# ice_drifter_6.net
KiCad netlist of a schematic drawn in EAGLE
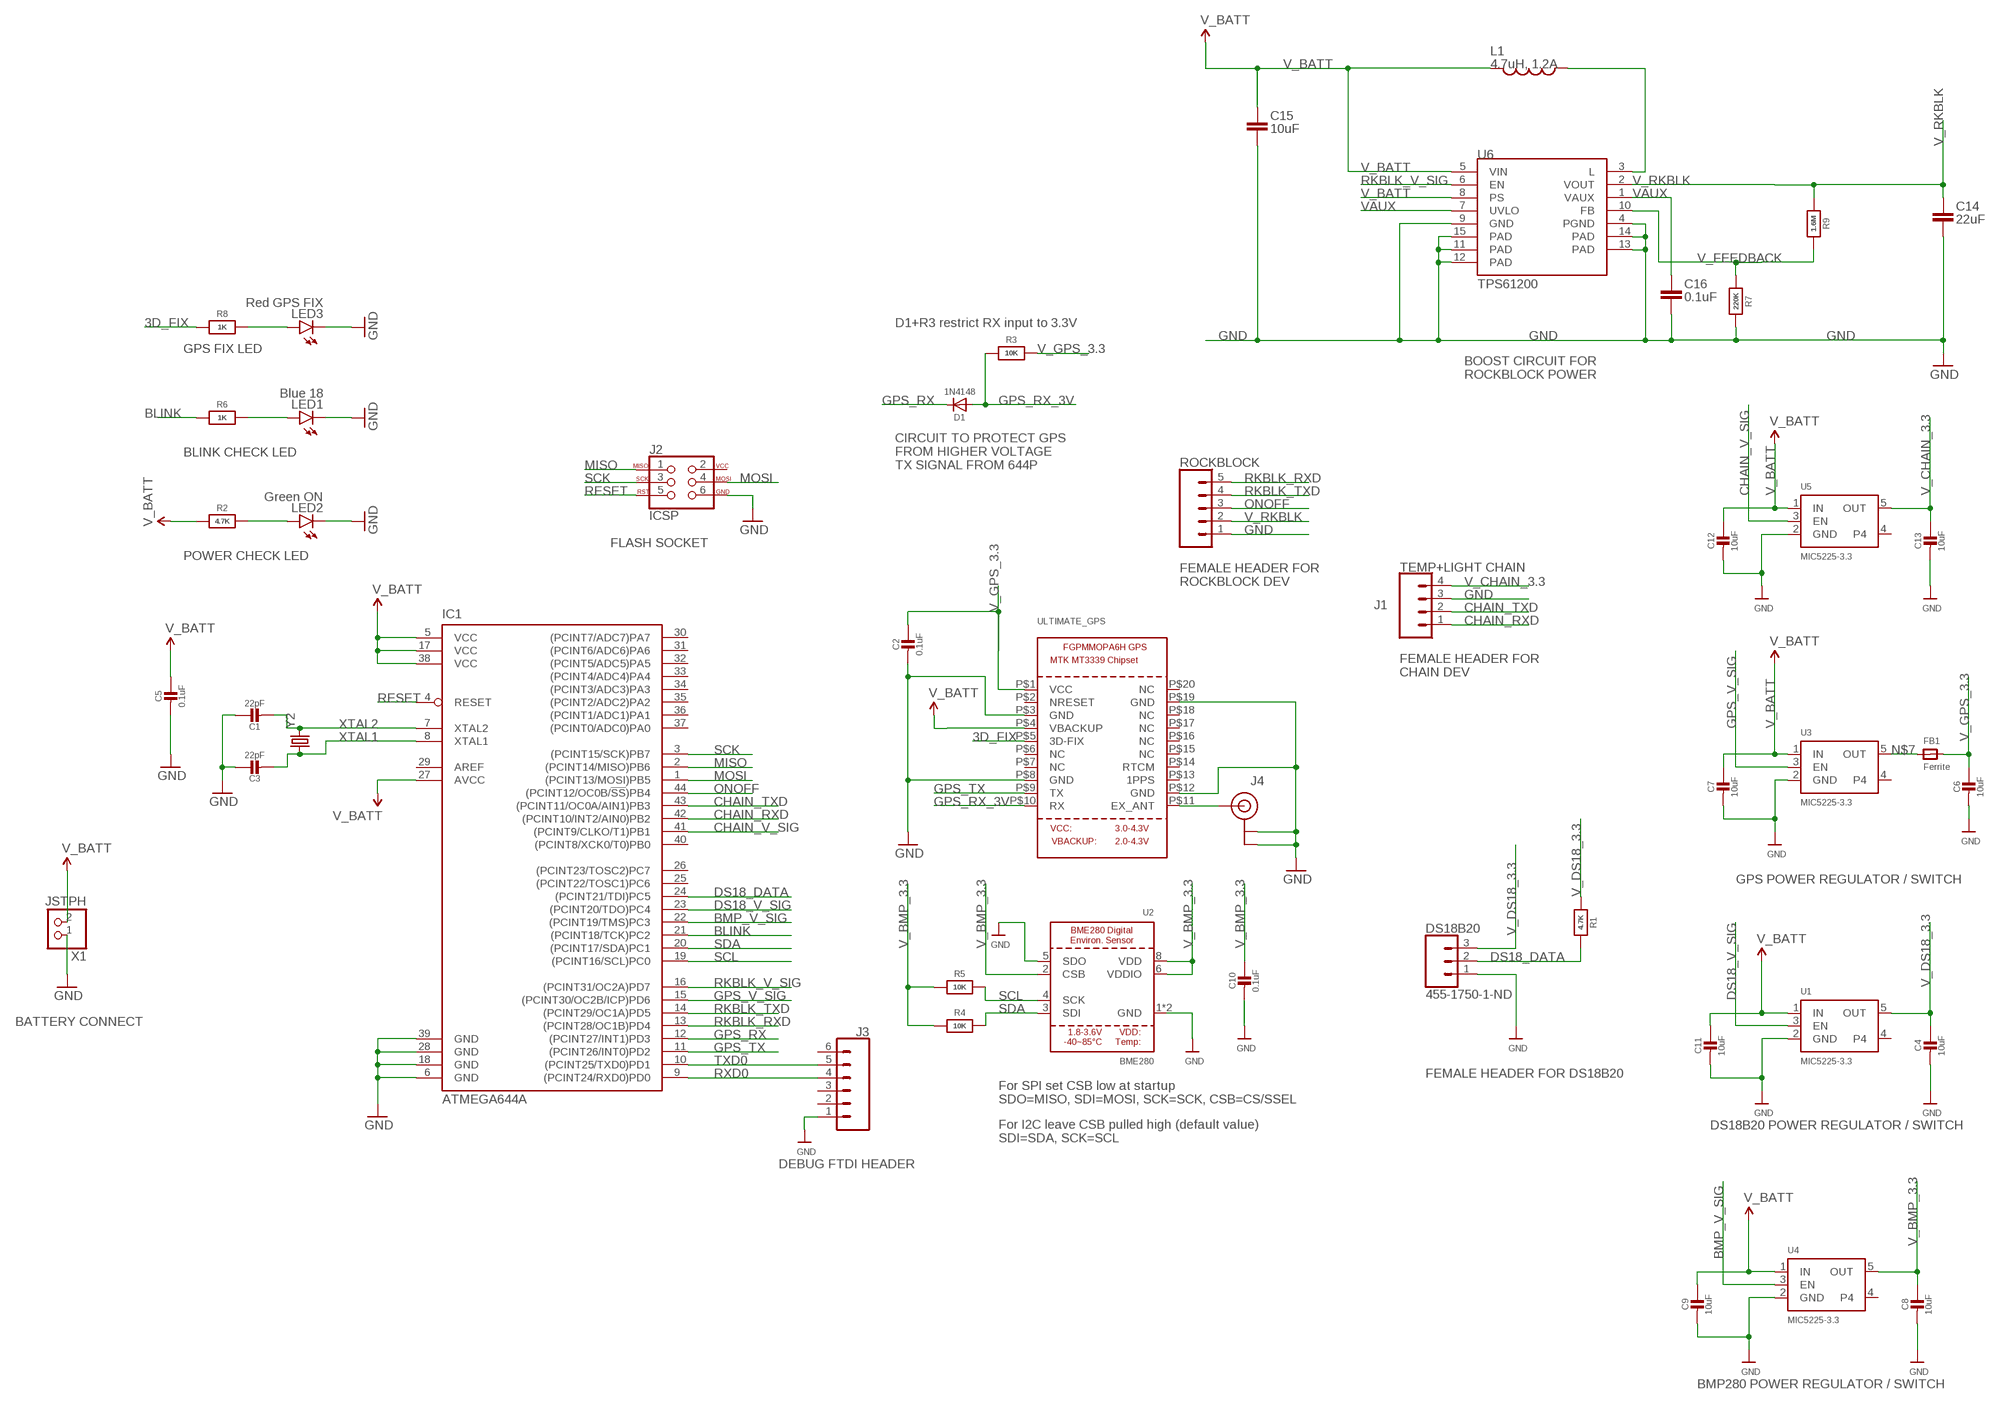
[diagram p0: schematic, sheet 1]

(export (version "E")
  (design (tool "Eeschema 10.0.6"))
  (components
    (comp (ref "C1")
      (value "22pF")
      (footprint "eagle-import:0805-NO@2")
      (libsource (lib "eagle-import") (part "CAP_CERAMIC0805-NOOUTLINE"))
    )
    (comp (ref "C2")
      (value "0.1uF")
      (footprint "eagle-import:0805-NO@2")
      (libsource (lib "eagle-import") (part "CAP_CERAMIC0805-NOOUTLINE"))
    )
    (comp (ref "C3")
      (value "22pF")
      (footprint "eagle-import:0805-NO@2")
      (libsource (lib "eagle-import") (part "CAP_CERAMIC0805-NOOUTLINE"))
    )
    (comp (ref "C4")
      (value "10uF")
      (footprint "eagle-import:0805-NO@2")
      (libsource (lib "eagle-import") (part "CAP_CERAMIC0805-NOOUTLINE"))
    )
    (comp (ref "C5")
      (value "0.1uF")
      (footprint "eagle-import:0805-NO@2")
      (libsource (lib "eagle-import") (part "CAP_CERAMIC0805-NOOUTLINE"))
    )
    (comp (ref "C6")
      (value "10uF")
      (footprint "eagle-import:0805-NO@2")
      (libsource (lib "eagle-import") (part "CAP_CERAMIC0805-NOOUTLINE"))
    )
    (comp (ref "C7")
      (value "10uF")
      (footprint "eagle-import:0805-NO@2")
      (libsource (lib "eagle-import") (part "CAP_CERAMIC0805-NOOUTLINE"))
    )
    (comp (ref "C8")
      (value "10uF")
      (footprint "eagle-import:0805-NO@2")
      (libsource (lib "eagle-import") (part "CAP_CERAMIC0805-NOOUTLINE"))
    )
    (comp (ref "C9")
      (value "10uF")
      (footprint "eagle-import:0805-NO@2")
      (libsource (lib "eagle-import") (part "CAP_CERAMIC0805-NOOUTLINE"))
    )
    (comp (ref "C10")
      (value "0.1uF")
      (footprint "eagle-import:0805-NO@2")
      (libsource (lib "eagle-import") (part "CAP_CERAMIC0805-NOOUTLINE"))
    )
    (comp (ref "C11")
      (value "10uF")
      (footprint "eagle-import:0805-NO@2")
      (libsource (lib "eagle-import") (part "CAP_CERAMIC0805-NOOUTLINE"))
    )
    (comp (ref "C12")
      (value "10uF")
      (footprint "eagle-import:0805-NO@2")
      (libsource (lib "eagle-import") (part "CAP_CERAMIC0805-NOOUTLINE"))
    )
    (comp (ref "C13")
      (value "10uF")
      (footprint "eagle-import:0805-NO@2")
      (libsource (lib "eagle-import") (part "CAP_CERAMIC0805-NOOUTLINE"))
    )
    (comp (ref "C14")
      (value "22uF")
      (footprint "eagle-import:0805")
      (libsource (lib "eagle-import") (part "CAP0805"))
    )
    (comp (ref "C15")
      (value "10uF")
      (footprint "eagle-import:1206")
      (libsource (lib "eagle-import") (part "CAP1206"))
    )
    (comp (ref "C16")
      (value "0.1uF")
      (footprint "eagle-import:0805")
      (libsource (lib "eagle-import") (part "CAP0805"))
    )
    (comp (ref "D1")
      (value "1N4148")
      (footprint "eagle-import:SOD-323")
      (libsource (lib "eagle-import") (part "DIODESOD-323"))
    )
    (comp (ref "DS18B20")
      (value "455-1750-1-ND")
      (footprint "eagle-import:1X03")
      (libsource (lib "eagle-import") (part "CONN_03"))
    )
    (comp (ref "FB1")
      (value "Ferrite")
      (footprint "eagle-import:0805-NO@1")
      (libsource (lib "eagle-import") (part "FERRITE-0805NO"))
    )
    (comp (ref "IC1")
      (value "ATMEGA644A")
      (footprint "eagle-import:TQFP44")
      (fields (field (name "MPN") "ATMEGA644PV-10AU"))
      (libsource (lib "eagle-import") (part "ATMEGA644A"))
    )
    (comp (ref "J1")
      (value "TEMP+LIGHT CHAIN")
      (footprint "eagle-import:1X04")
      (libsource (lib "eagle-import") (part "CONN_04"))
    )
    (comp (ref "J2")
      (value "ICSP")
      (footprint "eagle-import:2X3-NS")
      (libsource (lib "eagle-import") (part "AVR_SPI_PROG_3X2NS"))
    )
    (comp (ref "J3")
      (value "CONN_06SILK_FEMALE_PTH")
      (footprint "eagle-import:1X06")
      (libsource (lib "eagle-import") (part "CONN_06SILK_FEMALE_PTH"))
    )
    (comp (ref "J4")
      (value "U.FL")
      (footprint "eagle-import:U.FL")
      (libsource (lib "eagle-import") (part "U.FL"))
    )
    (comp (ref "L1")
      (value "4.7uH, 1.2A")
      (footprint "eagle-import:CDRH2D09")
      (libsource (lib "eagle-import") (part "INDUCTOR."))
    )
    (comp (ref "LED1")
      (value "Blue 18")
      (footprint "eagle-import:LED-1206")
      (libsource (lib "eagle-import") (part "LED1206"))
    )
    (comp (ref "LED2")
      (value "Green ON")
      (footprint "eagle-import:LED-1206")
      (libsource (lib "eagle-import") (part "LED1206"))
    )
    (comp (ref "LED3")
      (value "Red GPS FIX")
      (footprint "eagle-import:LED-1206")
      (libsource (lib "eagle-import") (part "LED1206"))
    )
    (comp (ref "R1")
      (value "4.7K")
      (footprint "eagle-import:0805-NO")
      (libsource (lib "eagle-import") (part "RESISTOR0805_NOOUTLINE"))
    )
    (comp (ref "R2")
      (value "4.7K")
      (footprint "eagle-import:0805-NO")
      (libsource (lib "eagle-import") (part "RESISTOR0805_NOOUTLINE"))
    )
    (comp (ref "R3")
      (value "10K")
      (footprint "eagle-import:0805-NO")
      (libsource (lib "eagle-import") (part "RESISTOR0805_NOOUTLINE"))
    )
    (comp (ref "R4")
      (value "10K")
      (footprint "eagle-import:0805-NO")
      (libsource (lib "eagle-import") (part "RESISTOR0805_NOOUTLINE"))
    )
    (comp (ref "R5")
      (value "10K")
      (footprint "eagle-import:0805-NO")
      (libsource (lib "eagle-import") (part "RESISTOR0805_NOOUTLINE"))
    )
    (comp (ref "R6")
      (value "1K")
      (footprint "eagle-import:0805-NO")
      (libsource (lib "eagle-import") (part "RESISTOR0805_NOOUTLINE"))
    )
    (comp (ref "R7")
      (value "220K")
      (footprint "eagle-import:0805-NO")
      (libsource (lib "eagle-import") (part "RESISTOR0805_NOOUTLINE"))
    )
    (comp (ref "R8")
      (value "1K")
      (footprint "eagle-import:0805-NO")
      (libsource (lib "eagle-import") (part "RESISTOR0805_NOOUTLINE"))
    )
    (comp (ref "R9")
      (value "1.6M")
      (footprint "eagle-import:0805-NO")
      (libsource (lib "eagle-import") (part "RESISTOR0805_NOOUTLINE"))
    )
    (comp (ref "ROCKBLOCK")
      (value "CONN_05")
      (footprint "eagle-import:1X05")
      (libsource (lib "eagle-import") (part "CONN_05"))
    )
    (comp (ref "U1")
      (value "MIC5225-3.3")
      (footprint "eagle-import:SOT23-5")
      (libsource (lib "eagle-import") (part "VREG_SOT23-5"))
    )
    (comp (ref "U2")
      (value "BME280")
      (footprint "eagle-import:BME280")
      (libsource (lib "eagle-import") (part "BME280"))
    )
    (comp (ref "U3")
      (value "MIC5225-3.3")
      (footprint "eagle-import:SOT23-5")
      (libsource (lib "eagle-import") (part "VREG_SOT23-5"))
    )
    (comp (ref "U4")
      (value "MIC5225-3.3")
      (footprint "eagle-import:SOT23-5")
      (libsource (lib "eagle-import") (part "VREG_SOT23-5"))
    )
    (comp (ref "U5")
      (value "MIC5225-3.3")
      (footprint "eagle-import:SOT23-5")
      (libsource (lib "eagle-import") (part "VREG_SOT23-5"))
    )
    (comp (ref "U6")
      (value "TPS61200")
      (footprint "eagle-import:QFN-10_PAD")
      (libsource (lib "eagle-import") (part "TPS61200"))
    )
    (comp (ref "ULTIMATE_GPS")
      (value "GPS_FGPMMOPA6H")
      (footprint "eagle-import:FGPMMOPA6H")
      (libsource (lib "eagle-import") (part "GPS_FGPMMOPA6H"))
    )
    (comp (ref "X1")
      (value "JSTPH")
      (footprint "eagle-import:JSTPH2")
      (libsource (lib "eagle-import") (part "CON_JST_PH_2PIN"))
    )
    (comp (ref "Y2")
      (value "CRYSTALTXC-7A")
      (footprint "eagle-import:CRYSTAL-TXC-7A")
      (libsource (lib "eagle-import") (part "CRYSTALTXC-7A"))
    )
  )
  (nets
    (net (code "1") (name "/3D_FIX") (class "Default")
      (node (ref "R8") (pin "1") (pinfunction "1_1") (pintype "passive"))
      (node (ref "ULTIMATE_GPS") (pin "P$5") (pinfunction "3D-FIX_P$5") (pintype "bidirectional"))
    )
    (net (code "2") (name "/BLINK") (class "Default")
      (node (ref "IC1") (pin "21") (pinfunction "(PCINT18/TCK)PC2_21") (pintype "output"))
      (node (ref "R6") (pin "1") (pinfunction "1_1") (pintype "passive"))
    )
    (net (code "3") (name "/BMP_V_SIG") (class "Default")
      (node (ref "IC1") (pin "22") (pinfunction "(PCINT19/TMS)PC3_22") (pintype "output"))
      (node (ref "U4") (pin "3") (pinfunction "EN_3") (pintype "input"))
    )
    (net (code "4") (name "/CHAIN_RXD") (class "Default")
      (node (ref "IC1") (pin "42") (pinfunction "(PCINT10/INT2/AIN0)PB2_42") (pintype "bidirectional"))
      (node (ref "J1") (pin "1") (pinfunction "1_1") (pintype "passive"))
    )
    (net (code "5") (name "/CHAIN_TXD") (class "Default")
      (node (ref "IC1") (pin "43") (pinfunction "(PCINT11/OC0A/AIN1)PB3_43") (pintype "bidirectional"))
      (node (ref "J1") (pin "2") (pinfunction "2_2") (pintype "passive"))
    )
    (net (code "6") (name "/CHAIN_V_SIG") (class "Default")
      (node (ref "IC1") (pin "41") (pinfunction "(PCINT9/CLKO/T1)PB1_41") (pintype "bidirectional"))
      (node (ref "U5") (pin "3") (pinfunction "EN_3") (pintype "input"))
    )
    (net (code "7") (name "/DS18_DATA") (class "Default")
      (node (ref "DS18B20") (pin "2") (pinfunction "2_2") (pintype "passive"))
      (node (ref "IC1") (pin "24") (pinfunction "(PCINT21/TDI)PC5_24") (pintype "output"))
      (node (ref "R1") (pin "2") (pinfunction "2_2") (pintype "passive"))
    )
    (net (code "8") (name "/DS18_V_SIG") (class "Default")
      (node (ref "IC1") (pin "23") (pinfunction "(PCINT20/TDO)PC4_23") (pintype "output"))
      (node (ref "U1") (pin "3") (pinfunction "EN_3") (pintype "input"))
    )
    (net (code "9") (name "/GPS_RX") (class "Default")
      (node (ref "D1") (pin "C") (pinfunction "C_C") (pintype "passive"))
      (node (ref "IC1") (pin "12") (pinfunction "(PCINT27/INT1)PD3_12") (pintype "bidirectional"))
    )
    (net (code "10") (name "/GPS_RX_3V") (class "Default")
      (node (ref "D1") (pin "A") (pinfunction "A_A") (pintype "passive"))
      (node (ref "R3") (pin "1") (pinfunction "1_1") (pintype "passive"))
      (node (ref "ULTIMATE_GPS") (pin "P$10") (pinfunction "RX_P$10") (pintype "bidirectional"))
    )
    (net (code "11") (name "/GPS_TX") (class "Default")
      (node (ref "IC1") (pin "11") (pinfunction "(PCINT26/INT0)PD2_11") (pintype "bidirectional"))
      (node (ref "ULTIMATE_GPS") (pin "P$9") (pinfunction "TX_P$9") (pintype "bidirectional"))
    )
    (net (code "12") (name "/GPS_V_SIG") (class "Default")
      (node (ref "IC1") (pin "15") (pinfunction "(PCINT30/OC2B/ICP)PD6_15") (pintype "bidirectional"))
      (node (ref "U3") (pin "3") (pinfunction "EN_3") (pintype "input"))
    )
    (net (code "13") (name "/MISO") (class "Default")
      (node (ref "IC1") (pin "2") (pinfunction "(PCINT14/MISO)PB6_2") (pintype "bidirectional"))
      (node (ref "J2") (pin "1") (pinfunction "1_1") (pintype "passive"))
    )
    (net (code "14") (name "/MOSI") (class "Default")
      (node (ref "IC1") (pin "1") (pinfunction "(PCINT13/MOSI)PB5_1") (pintype "bidirectional"))
      (node (ref "J2") (pin "4") (pinfunction "4_4") (pintype "passive"))
    )
    (net (code "15") (name "/N$7") (class "Default")
      (node (ref "FB1") (pin "1") (pinfunction "P$1_1") (pintype "passive"))
      (node (ref "U3") (pin "5") (pinfunction "OUT_5") (pintype "power_in"))
    )
    (net (code "16") (name "/ONOFF") (class "Default")
      (node (ref "IC1") (pin "44") (pinfunction "(PCINT12/OC0B/~{SS})PB4_44") (pintype "bidirectional"))
      (node (ref "ROCKBLOCK") (pin "3") (pinfunction "3_3") (pintype "passive"))
    )
    (net (code "17") (name "/RESET") (class "Default")
      (node (ref "IC1") (pin "4") (pinfunction "RESET_4") (pintype "input"))
      (node (ref "J2") (pin "5") (pinfunction "5_5") (pintype "passive"))
    )
    (net (code "18") (name "/RKBLK_RXD") (class "Default")
      (node (ref "IC1") (pin "13") (pinfunction "(PCINT28/OC1B)PD4_13") (pintype "bidirectional"))
      (node (ref "ROCKBLOCK") (pin "5") (pinfunction "5_5") (pintype "passive"))
    )
    (net (code "19") (name "/RKBLK_TXD") (class "Default")
      (node (ref "IC1") (pin "14") (pinfunction "(PCINT29/OC1A)PD5_14") (pintype "bidirectional"))
      (node (ref "ROCKBLOCK") (pin "4") (pinfunction "4_4") (pintype "passive"))
    )
    (net (code "20") (name "/RKBLK_V_SIG") (class "Default")
      (node (ref "IC1") (pin "16") (pinfunction "(PCINT31/OC2A)PD7_16") (pintype "bidirectional"))
      (node (ref "U6") (pin "6") (pinfunction "EN_6") (pintype "input"))
    )
    (net (code "21") (name "/RXD0") (class "Default")
      (node (ref "IC1") (pin "9") (pinfunction "(PCINT24/RXD0)PD0_9") (pintype "bidirectional"))
      (node (ref "J3") (pin "4") (pinfunction "4_4") (pintype "passive"))
    )
    (net (code "22") (name "/SCK") (class "Default")
      (node (ref "IC1") (pin "3") (pinfunction "(PCINT15/SCK)PB7_3") (pintype "bidirectional"))
      (node (ref "J2") (pin "3") (pinfunction "3_3") (pintype "passive"))
    )
    (net (code "23") (name "/SCL") (class "Default")
      (node (ref "IC1") (pin "19") (pinfunction "(PCINT16/SCL)PC0_19") (pintype "output"))
      (node (ref "R5") (pin "2") (pinfunction "2_2") (pintype "passive"))
      (node (ref "U2") (pin "4") (pinfunction "SCK_4") (pintype "input"))
    )
    (net (code "24") (name "/SDA") (class "Default")
      (node (ref "IC1") (pin "20") (pinfunction "(PCINT17/SDA)PC1_20") (pintype "output"))
      (node (ref "R4") (pin "2") (pinfunction "2_2") (pintype "passive"))
      (node (ref "U2") (pin "3") (pinfunction "SDI_3") (pintype "input"))
    )
    (net (code "25") (name "/TXD0") (class "Default")
      (node (ref "IC1") (pin "10") (pinfunction "(PCINT25/TXD0)PD1_10") (pintype "bidirectional"))
      (node (ref "J3") (pin "5") (pinfunction "5_5") (pintype "passive"))
    )
    (net (code "26") (name "/VAUX") (class "Default")
      (node (ref "C16") (pin "1") (pinfunction "1_1") (pintype "passive"))
      (node (ref "U6") (pin "1") (pinfunction "VAUX_1") (pintype "passive"))
      (node (ref "U6") (pin "7") (pinfunction "UVLO_7") (pintype "passive"))
    )
    (net (code "27") (name "/V_BMP_3.3") (class "Default")
      (node (ref "C10") (pin "1") (pinfunction "1_1") (pintype "passive"))
      (node (ref "C8") (pin "1") (pinfunction "1_1") (pintype "passive"))
      (node (ref "R4") (pin "1") (pinfunction "1_1") (pintype "passive"))
      (node (ref "R5") (pin "1") (pinfunction "1_1") (pintype "passive"))
      (node (ref "U2") (pin "2") (pinfunction "CSB_2") (pintype "input"))
      (node (ref "U2") (pin "6") (pinfunction "VDDIO_6") (pintype "power_in"))
      (node (ref "U2") (pin "8") (pinfunction "VDD_8") (pintype "power_in"))
      (node (ref "U4") (pin "5") (pinfunction "OUT_5") (pintype "power_in"))
    )
    (net (code "28") (name "/V_CHAIN_3.3") (class "Default")
      (node (ref "C13") (pin "1") (pinfunction "1_1") (pintype "passive"))
      (node (ref "J1") (pin "4") (pinfunction "4_4") (pintype "passive"))
      (node (ref "U5") (pin "5") (pinfunction "OUT_5") (pintype "power_in"))
    )
    (net (code "29") (name "/V_DS18_3.3") (class "Default")
      (node (ref "C4") (pin "1") (pinfunction "1_1") (pintype "passive"))
      (node (ref "DS18B20") (pin "3") (pinfunction "3_3") (pintype "passive"))
      (node (ref "R1") (pin "1") (pinfunction "1_1") (pintype "passive"))
      (node (ref "U1") (pin "5") (pinfunction "OUT_5") (pintype "power_in"))
    )
    (net (code "30") (name "/V_FEEDBACK") (class "Default")
      (node (ref "R7") (pin "1") (pinfunction "1_1") (pintype "passive"))
      (node (ref "R9") (pin "2") (pinfunction "2_2") (pintype "passive"))
      (node (ref "U6") (pin "10") (pinfunction "FB_10") (pintype "passive"))
    )
    (net (code "31") (name "/V_GPS_3.3") (class "Default")
      (node (ref "C2") (pin "1") (pinfunction "1_1") (pintype "passive"))
      (node (ref "C6") (pin "1") (pinfunction "1_1") (pintype "passive"))
      (node (ref "FB1") (pin "2") (pinfunction "P$2_2") (pintype "passive"))
      (node (ref "R3") (pin "2") (pinfunction "2_2") (pintype "passive"))
      (node (ref "ULTIMATE_GPS") (pin "P$1") (pinfunction "VCC_P$1") (pintype "bidirectional"))
    )
    (net (code "32") (name "/V_RKBLK") (class "Default")
      (node (ref "C14") (pin "1") (pinfunction "1_1") (pintype "passive"))
      (node (ref "R9") (pin "1") (pinfunction "1_1") (pintype "passive"))
      (node (ref "ROCKBLOCK") (pin "2") (pinfunction "2_2") (pintype "passive"))
      (node (ref "U6") (pin "2") (pinfunction "VOUT_2") (pintype "passive"))
    )
    (net (code "33") (name "/XTAL1") (class "Default")
      (node (ref "C3") (pin "2") (pinfunction "2_2") (pintype "passive"))
      (node (ref "IC1") (pin "8") (pinfunction "XTAL1_8") (pintype "bidirectional"))
      (node (ref "Y2") (pin "P$1") (pinfunction "1_P$1") (pintype "passive"))
    )
    (net (code "34") (name "/XTAL2") (class "Default")
      (node (ref "C1") (pin "2") (pinfunction "2_2") (pintype "passive"))
      (node (ref "IC1") (pin "7") (pinfunction "XTAL2_7") (pintype "bidirectional"))
      (node (ref "Y2") (pin "P$2") (pinfunction "2_P$2") (pintype "passive"))
    )
    (net (code "35") (name "GND") (class "Default")
      (node (ref "C1") (pin "1") (pinfunction "1_1") (pintype "passive"))
      (node (ref "C10") (pin "2") (pinfunction "2_2") (pintype "passive"))
      (node (ref "C11") (pin "2") (pinfunction "2_2") (pintype "passive"))
      (node (ref "C12") (pin "2") (pinfunction "2_2") (pintype "passive"))
      (node (ref "C13") (pin "2") (pinfunction "2_2") (pintype "passive"))
      (node (ref "C14") (pin "2") (pinfunction "2_2") (pintype "passive"))
      (node (ref "C15") (pin "2") (pinfunction "2_2") (pintype "passive"))
      (node (ref "C16") (pin "2") (pinfunction "2_2") (pintype "passive"))
      (node (ref "C2") (pin "2") (pinfunction "2_2") (pintype "passive"))
      (node (ref "C3") (pin "1") (pinfunction "1_1") (pintype "passive"))
      (node (ref "C4") (pin "2") (pinfunction "2_2") (pintype "passive"))
      (node (ref "C5") (pin "2") (pinfunction "2_2") (pintype "passive"))
      (node (ref "C6") (pin "2") (pinfunction "2_2") (pintype "passive"))
      (node (ref "C7") (pin "2") (pinfunction "2_2") (pintype "passive"))
      (node (ref "C8") (pin "2") (pinfunction "2_2") (pintype "passive"))
      (node (ref "C9") (pin "2") (pinfunction "2_2") (pintype "passive"))
      (node (ref "DS18B20") (pin "1") (pinfunction "1_1") (pintype "passive"))
      (node (ref "IC1") (pin "18") (pinfunction "GND_18") (pintype "power_in"))
      (node (ref "IC1") (pin "28") (pinfunction "GND_28") (pintype "power_in"))
      (node (ref "IC1") (pin "39") (pinfunction "GND_39") (pintype "power_in"))
      (node (ref "IC1") (pin "6") (pinfunction "GND_6") (pintype "power_in"))
      (node (ref "J1") (pin "3") (pinfunction "3_3") (pintype "passive"))
      (node (ref "J2") (pin "6") (pinfunction "6_6") (pintype "passive"))
      (node (ref "J3") (pin "1") (pinfunction "1_1") (pintype "passive"))
      (node (ref "J4") (pin "1") (pinfunction "GND_1") (pintype "bidirectional"))
      (node (ref "J4") (pin "2") (pinfunction "GND_2") (pintype "bidirectional"))
      (node (ref "LED1") (pin "C") (pinfunction "C_C") (pintype "passive"))
      (node (ref "LED2") (pin "C") (pinfunction "C_C") (pintype "passive"))
      (node (ref "LED3") (pin "C") (pinfunction "C_C") (pintype "passive"))
      (node (ref "R7") (pin "2") (pinfunction "2_2") (pintype "passive"))
      (node (ref "ROCKBLOCK") (pin "1") (pinfunction "1_1") (pintype "passive"))
      (node (ref "U1") (pin "2") (pinfunction "GND_2") (pintype "power_in"))
      (node (ref "U2") (pin "1") (pinfunction "GND_1") (pintype "power_in"))
      (node (ref "U2") (pin "5") (pinfunction "SDO_5") (pintype "output"))
      (node (ref "U2") (pin "7") (pinfunction "GND_7") (pintype "power_in"))
      (node (ref "U3") (pin "2") (pinfunction "GND_2") (pintype "power_in"))
      (node (ref "U4") (pin "2") (pinfunction "GND_2") (pintype "power_in"))
      (node (ref "U5") (pin "2") (pinfunction "GND_2") (pintype "power_in"))
      (node (ref "U6") (pin "11") (pinfunction "PAD_11") (pintype "power_in"))
      (node (ref "U6") (pin "12") (pinfunction "PAD_12") (pintype "power_in"))
      (node (ref "U6") (pin "13") (pinfunction "PAD_13") (pintype "power_in"))
      (node (ref "U6") (pin "14") (pinfunction "PAD_14") (pintype "power_in"))
      (node (ref "U6") (pin "15") (pinfunction "PAD_15") (pintype "power_in"))
      (node (ref "U6") (pin "4") (pinfunction "PGND_4") (pintype "power_in"))
      (node (ref "U6") (pin "9") (pinfunction "GND_9") (pintype "power_in"))
      (node (ref "ULTIMATE_GPS") (pin "P$12") (pinfunction "GND_P$12") (pintype "bidirectional"))
      (node (ref "ULTIMATE_GPS") (pin "P$19") (pinfunction "GND_P$19") (pintype "bidirectional"))
      (node (ref "ULTIMATE_GPS") (pin "P$3") (pinfunction "GND_P$3") (pintype "bidirectional"))
      (node (ref "ULTIMATE_GPS") (pin "P$8") (pinfunction "GND_P$8") (pintype "bidirectional"))
      (node (ref "X1") (pin "1") (pinfunction "1_1") (pintype "passive"))
    )
    (net (code "36") (name "Net-(J4-SIGNAL)") (class "Default")
      (node (ref "J4") (pin "FEED") (pinfunction "SIGNAL_FEED") (pintype "bidirectional"))
      (node (ref "ULTIMATE_GPS") (pin "P$11") (pinfunction "EX_ANT_P$11") (pintype "bidirectional"))
    )
    (net (code "37") (name "Net-(L1-1)") (class "Default")
      (node (ref "L1") (pin "P$1") (pinfunction "1_P$1") (pintype "passive"))
      (node (ref "U6") (pin "3") (pinfunction "L_3") (pintype "passive"))
    )
    (net (code "38") (name "Net-(LED1-PadA)") (class "Default")
      (node (ref "LED1") (pin "A") (pinfunction "A_A") (pintype "passive"))
      (node (ref "R6") (pin "2") (pinfunction "2_2") (pintype "passive"))
    )
    (net (code "39") (name "Net-(LED2-PadA)") (class "Default")
      (node (ref "LED2") (pin "A") (pinfunction "A_A") (pintype "passive"))
      (node (ref "R2") (pin "2") (pinfunction "2_2") (pintype "passive"))
    )
    (net (code "40") (name "Net-(LED3-PadA)") (class "Default")
      (node (ref "LED3") (pin "A") (pinfunction "A_A") (pintype "passive"))
      (node (ref "R8") (pin "2") (pinfunction "2_2") (pintype "passive"))
    )
    (net (code "41") (name "V_BATT") (class "Default")
      (node (ref "C11") (pin "1") (pinfunction "1_1") (pintype "passive"))
      (node (ref "C12") (pin "1") (pinfunction "1_1") (pintype "passive"))
      (node (ref "C15") (pin "1") (pinfunction "1_1") (pintype "passive"))
      (node (ref "C5") (pin "1") (pinfunction "1_1") (pintype "passive"))
      (node (ref "C7") (pin "1") (pinfunction "1_1") (pintype "passive"))
      (node (ref "C9") (pin "1") (pinfunction "1_1") (pintype "passive"))
      (node (ref "IC1") (pin "17") (pinfunction "VCC_17") (pintype "power_in"))
      (node (ref "IC1") (pin "27") (pinfunction "AVCC_27") (pintype "power_in"))
      (node (ref "IC1") (pin "38") (pinfunction "VCC_38") (pintype "power_in"))
      (node (ref "IC1") (pin "5") (pinfunction "VCC_5") (pintype "power_in"))
      (node (ref "L1") (pin "P$2") (pinfunction "2_P$2") (pintype "passive"))
      (node (ref "R2") (pin "1") (pinfunction "1_1") (pintype "passive"))
      (node (ref "U1") (pin "1") (pinfunction "IN_1") (pintype "power_in"))
      (node (ref "U3") (pin "1") (pinfunction "IN_1") (pintype "power_in"))
      (node (ref "U4") (pin "1") (pinfunction "IN_1") (pintype "power_in"))
      (node (ref "U5") (pin "1") (pinfunction "IN_1") (pintype "power_in"))
      (node (ref "U6") (pin "5") (pinfunction "VIN_5") (pintype "power_in"))
      (node (ref "U6") (pin "8") (pinfunction "PS_8") (pintype "input"))
      (node (ref "ULTIMATE_GPS") (pin "P$4") (pinfunction "VBACKUP_P$4") (pintype "bidirectional"))
      (node (ref "X1") (pin "2") (pinfunction "2_2") (pintype "passive"))
    )
    (net (code "42") (name "unconnected-(IC1-(PCINT0{slash}ADC0)PA0-Pad37)") (class "Default")
      (node (ref "IC1") (pin "37") (pinfunction "(PCINT0/ADC0)PA0_37") (pintype "bidirectional"))
    )
    (net (code "43") (name "unconnected-(IC1-(PCINT1{slash}ADC1)PA1-Pad36)") (class "Default")
      (node (ref "IC1") (pin "36") (pinfunction "(PCINT1/ADC1)PA1_36") (pintype "bidirectional"))
    )
    (net (code "44") (name "unconnected-(IC1-(PCINT2{slash}ADC2)PA2-Pad35)") (class "Default")
      (node (ref "IC1") (pin "35") (pinfunction "(PCINT2/ADC2)PA2_35") (pintype "bidirectional"))
    )
    (net (code "45") (name "unconnected-(IC1-(PCINT3{slash}ADC3)PA3-Pad34)") (class "Default")
      (node (ref "IC1") (pin "34") (pinfunction "(PCINT3/ADC3)PA3_34") (pintype "bidirectional"))
    )
    (net (code "46") (name "unconnected-(IC1-(PCINT4{slash}ADC4)PA4-Pad33)") (class "Default")
      (node (ref "IC1") (pin "33") (pinfunction "(PCINT4/ADC4)PA4_33") (pintype "bidirectional"))
    )
    (net (code "47") (name "unconnected-(IC1-(PCINT5{slash}ADC5)PA5-Pad32)") (class "Default")
      (node (ref "IC1") (pin "32") (pinfunction "(PCINT5/ADC5)PA5_32") (pintype "bidirectional"))
    )
    (net (code "48") (name "unconnected-(IC1-(PCINT6{slash}ADC6)PA6-Pad31)") (class "Default")
      (node (ref "IC1") (pin "31") (pinfunction "(PCINT6/ADC6)PA6_31") (pintype "bidirectional"))
    )
    (net (code "49") (name "unconnected-(IC1-(PCINT7{slash}ADC7)PA7-Pad30)") (class "Default")
      (node (ref "IC1") (pin "30") (pinfunction "(PCINT7/ADC7)PA7_30") (pintype "bidirectional"))
    )
    (net (code "50") (name "unconnected-(IC1-(PCINT8{slash}XCK0{slash}T0)PB0-Pad40)") (class "Default")
      (node (ref "IC1") (pin "40") (pinfunction "(PCINT8/XCK0/T0)PB0_40") (pintype "bidirectional"))
    )
    (net (code "51") (name "unconnected-(IC1-(PCINT22{slash}TOSC1)PC6-Pad25)") (class "Default")
      (node (ref "IC1") (pin "25") (pinfunction "(PCINT22/TOSC1)PC6_25") (pintype "output"))
    )
    (net (code "52") (name "unconnected-(IC1-(PCINT23{slash}TOSC2)PC7-Pad26)") (class "Default")
      (node (ref "IC1") (pin "26") (pinfunction "(PCINT23/TOSC2)PC7_26") (pintype "output"))
    )
    (net (code "53") (name "unconnected-(IC1-AREF-Pad29)") (class "Default")
      (node (ref "IC1") (pin "29") (pinfunction "AREF_29") (pintype "passive"))
    )
    (net (code "54") (name "unconnected-(J2-Pad2)") (class "Default")
      (node (ref "J2") (pin "2") (pinfunction "2_2") (pintype "passive"))
    )
    (net (code "55") (name "unconnected-(J3-Pad2)") (class "Default")
      (node (ref "J3") (pin "2") (pinfunction "2_2") (pintype "passive"))
    )
    (net (code "56") (name "unconnected-(J3-Pad3)") (class "Default")
      (node (ref "J3") (pin "3") (pinfunction "3_3") (pintype "passive"))
    )
    (net (code "57") (name "unconnected-(J3-Pad6)") (class "Default")
      (node (ref "J3") (pin "6") (pinfunction "6_6") (pintype "passive"))
    )
    (net (code "58") (name "unconnected-(U1-P4-Pad4)") (class "Default")
      (node (ref "U1") (pin "4") (pinfunction "P4_4") (pintype "bidirectional"))
    )
    (net (code "59") (name "unconnected-(U3-P4-Pad4)") (class "Default")
      (node (ref "U3") (pin "4") (pinfunction "P4_4") (pintype "bidirectional"))
    )
    (net (code "60") (name "unconnected-(U4-P4-Pad4)") (class "Default")
      (node (ref "U4") (pin "4") (pinfunction "P4_4") (pintype "bidirectional"))
    )
    (net (code "61") (name "unconnected-(U5-P4-Pad4)") (class "Default")
      (node (ref "U5") (pin "4") (pinfunction "P4_4") (pintype "bidirectional"))
    )
    (net (code "62") (name "unconnected-(ULTIMATE_GPS-1PPS-PadP$13)") (class "Default")
      (node (ref "ULTIMATE_GPS") (pin "P$13") (pinfunction "1PPS_P$13") (pintype "bidirectional"))
    )
    (net (code "63") (name "unconnected-(ULTIMATE_GPS-NC-PadP$6)") (class "Default")
      (node (ref "ULTIMATE_GPS") (pin "P$6") (pinfunction "NC_P$6") (pintype "bidirectional"))
    )
    (net (code "64") (name "unconnected-(ULTIMATE_GPS-NC-PadP$7)") (class "Default")
      (node (ref "ULTIMATE_GPS") (pin "P$7") (pinfunction "NC_P$7") (pintype "bidirectional"))
    )
    (net (code "65") (name "unconnected-(ULTIMATE_GPS-NC-PadP$15)") (class "Default")
      (node (ref "ULTIMATE_GPS") (pin "P$15") (pinfunction "NC_P$15") (pintype "bidirectional"))
    )
    (net (code "66") (name "unconnected-(ULTIMATE_GPS-NC-PadP$16)") (class "Default")
      (node (ref "ULTIMATE_GPS") (pin "P$16") (pinfunction "NC_P$16") (pintype "bidirectional"))
    )
    (net (code "67") (name "unconnected-(ULTIMATE_GPS-NC-PadP$17)") (class "Default")
      (node (ref "ULTIMATE_GPS") (pin "P$17") (pinfunction "NC_P$17") (pintype "bidirectional"))
    )
    (net (code "68") (name "unconnected-(ULTIMATE_GPS-NC-PadP$18)") (class "Default")
      (node (ref "ULTIMATE_GPS") (pin "P$18") (pinfunction "NC_P$18") (pintype "bidirectional"))
    )
    (net (code "69") (name "unconnected-(ULTIMATE_GPS-NC-PadP$20)") (class "Default")
      (node (ref "ULTIMATE_GPS") (pin "P$20") (pinfunction "NC_P$20") (pintype "bidirectional"))
    )
    (net (code "70") (name "unconnected-(ULTIMATE_GPS-NRESET-PadP$2)") (class "Default")
      (node (ref "ULTIMATE_GPS") (pin "P$2") (pinfunction "NRESET_P$2") (pintype "bidirectional"))
    )
    (net (code "71") (name "unconnected-(ULTIMATE_GPS-RTCM-PadP$14)") (class "Default")
      (node (ref "ULTIMATE_GPS") (pin "P$14") (pinfunction "RTCM_P$14") (pintype "bidirectional"))
    )
  )
)
